# OC2_2boards.net
KiCad netlist of a schematic drawn in EAGLE
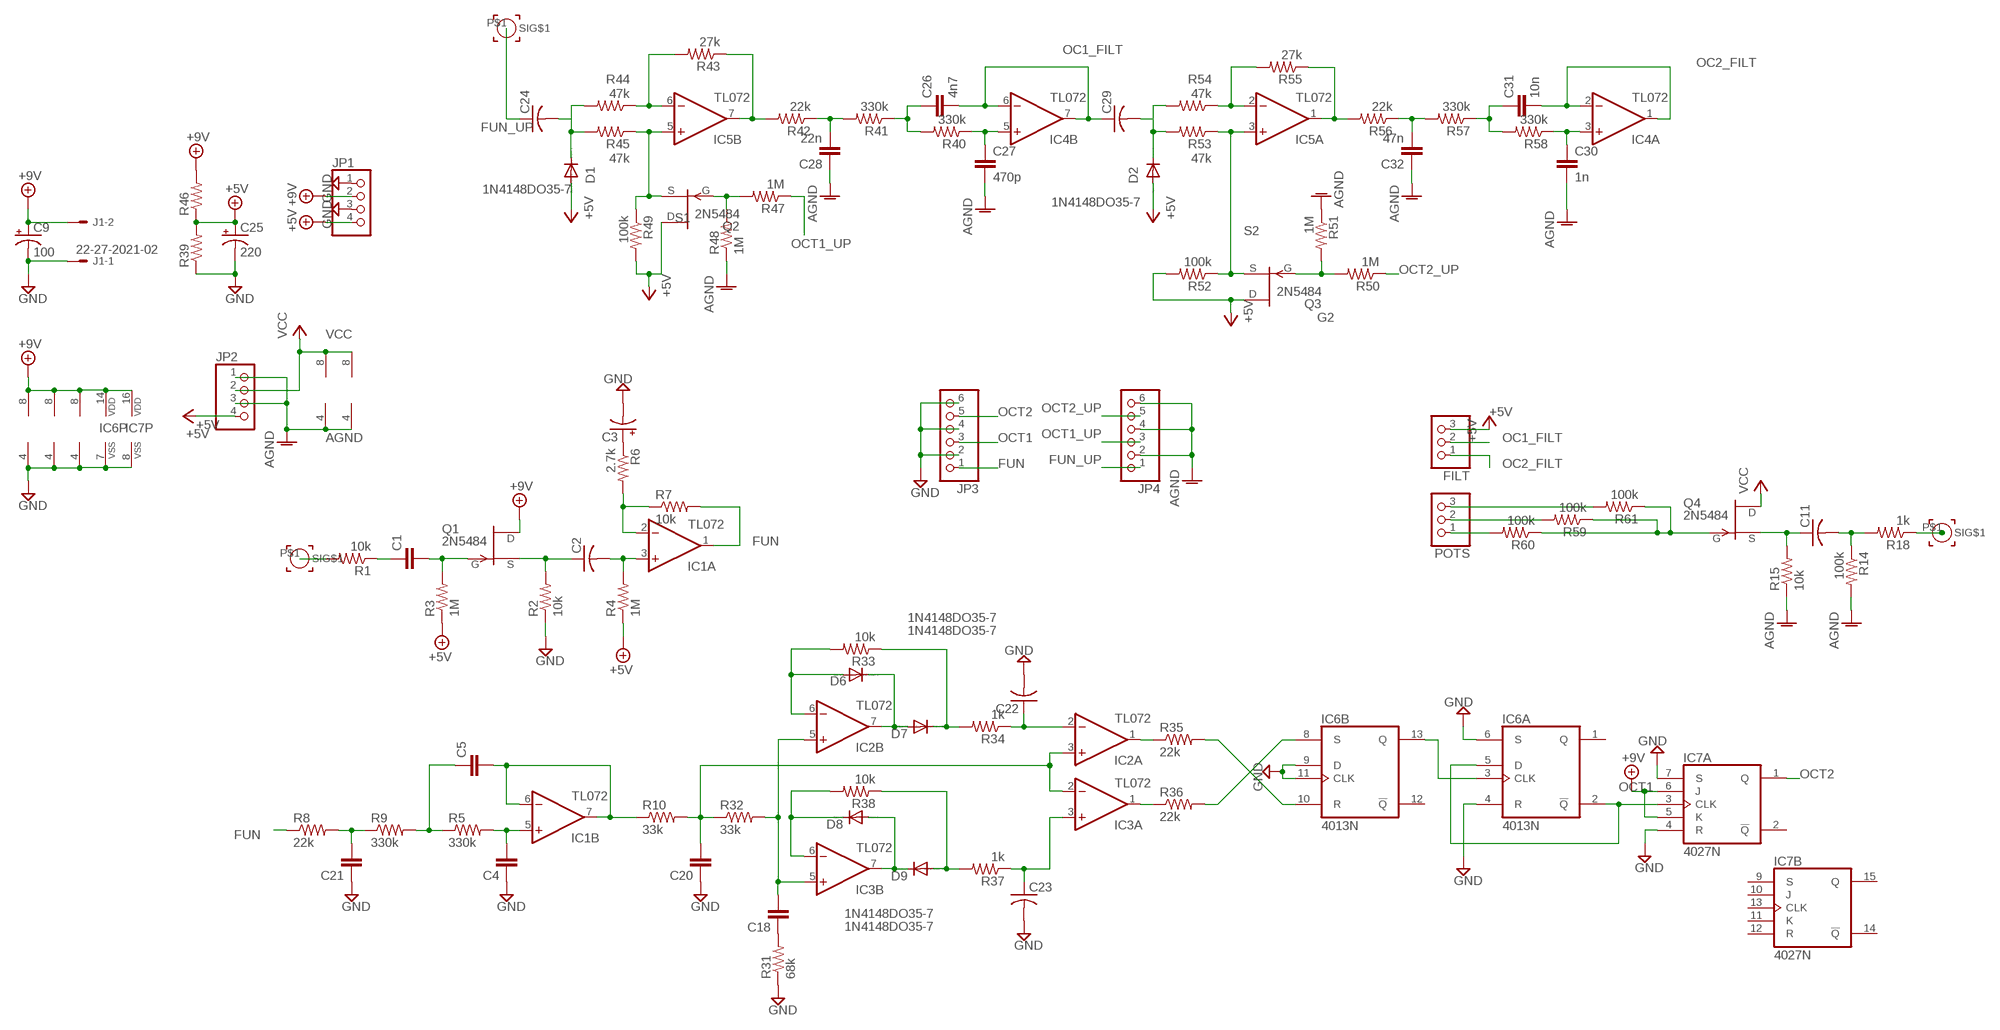
[diagram p0: schematic, sheet 1]

(export (version "E")
  (design (tool "Eeschema 10.0.6"))
  (components
    (comp (ref "C1")
      (value "C-EU")
      (footprint "eagle-import:C025-025X050-BP")
      (libsource (lib "eagle-import") (part "C-EU"))
    )
    (comp (ref "C2")
      (value "C-US")
      (footprint "eagle-import:C050-024X044-BP")
      (libsource (lib "eagle-import") (part "C-US"))
    )
    (comp (ref "C3")
      (value "CPOL-USE2.5-5")
      (footprint "eagle-import:E2,5-5")
      (libsource (lib "eagle-import") (part "CPOL-USE2.5-5"))
    )
    (comp (ref "C4")
      (value "C-EU")
      (footprint "eagle-import:C025-025X050-BP")
      (libsource (lib "eagle-import") (part "C-EU"))
    )
    (comp (ref "C5")
      (value "C-EU")
      (footprint "eagle-import:C025-025X050-BP")
      (libsource (lib "eagle-import") (part "C-EU"))
    )
    (comp (ref "C9")
      (value "100")
      (footprint "eagle-import:E2,5-6")
      (libsource (lib "eagle-import") (part "CPOL-USE2.5-6"))
    )
    (comp (ref "C11")
      (value "C-US")
      (footprint "eagle-import:C050-024X044-BP")
      (libsource (lib "eagle-import") (part "C-US"))
    )
    (comp (ref "C18")
      (value "C-EU")
      (footprint "eagle-import:C025-025X050-BP")
      (libsource (lib "eagle-import") (part "C-EU"))
    )
    (comp (ref "C20")
      (value "C-EU")
      (footprint "eagle-import:C025-025X050-BP")
      (libsource (lib "eagle-import") (part "C-EU"))
    )
    (comp (ref "C21")
      (value "C-EU")
      (footprint "eagle-import:C025-025X050-BP")
      (libsource (lib "eagle-import") (part "C-EU"))
    )
    (comp (ref "C22")
      (value "C-US")
      (footprint "eagle-import:C050-024X044-BP")
      (libsource (lib "eagle-import") (part "C-US"))
    )
    (comp (ref "C23")
      (value "C-US")
      (footprint "eagle-import:C050-024X044-BP")
      (libsource (lib "eagle-import") (part "C-US"))
    )
    (comp (ref "C24")
      (value "C-US")
      (footprint "eagle-import:C050-024X044-BP")
      (libsource (lib "eagle-import") (part "C-US"))
    )
    (comp (ref "C25")
      (value "220")
      (footprint "eagle-import:E3,5-8")
      (libsource (lib "eagle-import") (part "CPOL-USE3.5-8"))
    )
    (comp (ref "C26")
      (value "4n7")
      (footprint "eagle-import:C025-025X050-BP")
      (libsource (lib "eagle-import") (part "C-EU"))
    )
    (comp (ref "C27")
      (value "470p")
      (footprint "eagle-import:C025-025X050-BP")
      (libsource (lib "eagle-import") (part "C-EU"))
    )
    (comp (ref "C28")
      (value "22n")
      (footprint "eagle-import:C025-025X050-BP")
      (libsource (lib "eagle-import") (part "C-EU"))
    )
    (comp (ref "C29")
      (value "C-US")
      (footprint "eagle-import:C050-024X044-BP")
      (libsource (lib "eagle-import") (part "C-US"))
    )
    (comp (ref "C30")
      (value "1n")
      (footprint "eagle-import:C025-025X050-BP")
      (libsource (lib "eagle-import") (part "C-EU"))
    )
    (comp (ref "C31")
      (value "10n")
      (footprint "eagle-import:C025-025X050-BP")
      (libsource (lib "eagle-import") (part "C-EU"))
    )
    (comp (ref "C32")
      (value "47n")
      (footprint "eagle-import:C025-025X050-BP")
      (libsource (lib "eagle-import") (part "C-EU"))
    )
    (comp (ref "D1")
      (value "1N4148DO35-7")
      (footprint "eagle-import:DO35-7")
      (libsource (lib "eagle-import") (part "1N4148DO35-7"))
    )
    (comp (ref "D2")
      (value "1N4148DO35-7")
      (footprint "eagle-import:DO35-7")
      (libsource (lib "eagle-import") (part "1N4148DO35-7"))
    )
    (comp (ref "D6")
      (value "1N4148DO35-7")
      (footprint "eagle-import:DO35-7")
      (libsource (lib "eagle-import") (part "1N4148DO35-7"))
    )
    (comp (ref "D7")
      (value "1N4148DO35-7")
      (footprint "eagle-import:DO35-7")
      (libsource (lib "eagle-import") (part "1N4148DO35-7"))
    )
    (comp (ref "D8")
      (value "1N4148DO35-7")
      (footprint "eagle-import:DO35-7")
      (libsource (lib "eagle-import") (part "1N4148DO35-7"))
    )
    (comp (ref "D9")
      (value "1N4148DO35-7")
      (footprint "eagle-import:DO35-7")
      (libsource (lib "eagle-import") (part "1N4148DO35-7"))
    )
    (comp (ref "FILT")
      (value "PINHD-1X3")
      (footprint "eagle-import:1X03")
      (libsource (lib "eagle-import") (part "PINHD-1X3"))
    )
    (comp (ref "IC1")
      (value "TL072")
      (footprint "eagle-import:DIL08-BP")
      (libsource (lib "eagle-import") (part "TL072"))
    )
    (comp (ref "IC2")
      (value "TL072")
      (footprint "eagle-import:DIL08-BP")
      (libsource (lib "eagle-import") (part "TL072"))
    )
    (comp (ref "IC3")
      (value "TL072")
      (footprint "eagle-import:DIL08-BP")
      (libsource (lib "eagle-import") (part "TL072"))
    )
    (comp (ref "IC4")
      (value "TL072")
      (footprint "eagle-import:DIL08-BP")
      (libsource (lib "eagle-import") (part "TL072"))
    )
    (comp (ref "IC5")
      (value "TL072")
      (footprint "eagle-import:DIL08-BP")
      (libsource (lib "eagle-import") (part "TL072"))
    )
    (comp (ref "IC6")
      (value "4013N")
      (footprint "eagle-import:DIL14")
      (libsource (lib "eagle-import") (part "4013N"))
    )
    (comp (ref "IC7")
      (value "4027N")
      (footprint "eagle-import:DIL16")
      (libsource (lib "eagle-import") (part "4027N"))
    )
    (comp (ref "INPUT")
      (value "SIGNAL_PAD")
      (footprint "eagle-import:SIGNAL_PAD")
      (libsource (lib "eagle-import") (part "SIGNAL_PAD"))
    )
    (comp (ref "INPUT1")
      (value "SIGNAL_PAD")
      (footprint "eagle-import:SIGNAL_PAD")
      (libsource (lib "eagle-import") (part "SIGNAL_PAD"))
    )
    (comp (ref "INPUT2")
      (value "SIGNAL_PAD")
      (footprint "eagle-import:SIGNAL_PAD")
      (libsource (lib "eagle-import") (part "SIGNAL_PAD"))
    )
    (comp (ref "J1")
      (value "22-27-2021-02")
      (footprint "eagle-import:6410-02")
      (libsource (lib "eagle-import") (part "22-?-0227-2021"))
    )
    (comp (ref "JP1")
      (value "PINHD-1X4")
      (footprint "eagle-import:1X04")
      (libsource (lib "eagle-import") (part "PINHD-1X4"))
    )
    (comp (ref "JP2")
      (value "PINHD-1X4")
      (footprint "eagle-import:1X04")
      (libsource (lib "eagle-import") (part "PINHD-1X4"))
    )
    (comp (ref "JP3")
      (value "PINHD-1X6")
      (footprint "eagle-import:1X06")
      (libsource (lib "eagle-import") (part "PINHD-1X6"))
    )
    (comp (ref "JP4")
      (value "PINHD-1X6")
      (footprint "eagle-import:1X06")
      (libsource (lib "eagle-import") (part "PINHD-1X6"))
    )
    (comp (ref "POTS")
      (value "PINHD-1X3")
      (footprint "eagle-import:1X03")
      (libsource (lib "eagle-import") (part "PINHD-1X3"))
    )
    (comp (ref "Q1")
      (value "2N5484")
      (footprint "eagle-import:TO92-")
      (libsource (lib "eagle-import") (part "?5482N4"))
    )
    (comp (ref "Q2")
      (value "2N5484")
      (footprint "eagle-import:TO92-")
      (libsource (lib "eagle-import") (part "?5482N4"))
    )
    (comp (ref "Q3")
      (value "2N5484")
      (footprint "eagle-import:TO92-")
      (libsource (lib "eagle-import") (part "?5482N4"))
    )
    (comp (ref "Q4")
      (value "2N5484")
      (footprint "eagle-import:TO92-")
      (libsource (lib "eagle-import") (part "?5482N4"))
    )
    (comp (ref "R1")
      (value "10k")
      (footprint "eagle-import:0204V-BP")
      (libsource (lib "eagle-import") (part "R-US_0204/2V-BP"))
    )
    (comp (ref "R2")
      (value "10k")
      (footprint "eagle-import:0204V-BP")
      (libsource (lib "eagle-import") (part "R-US_0204/2V-BP"))
    )
    (comp (ref "R3")
      (value "1M")
      (footprint "eagle-import:0204V-BP")
      (libsource (lib "eagle-import") (part "R-US_0204/2V-BP"))
    )
    (comp (ref "R4")
      (value "1M")
      (footprint "eagle-import:0204_5-BP")
      (libsource (lib "eagle-import") (part "R-US_0204/5-BP"))
    )
    (comp (ref "R5")
      (value "330k")
      (footprint "eagle-import:0204V-BP")
      (libsource (lib "eagle-import") (part "R-US_0204/2V-BP"))
    )
    (comp (ref "R6")
      (value "2.7k")
      (footprint "eagle-import:0204V-BP")
      (libsource (lib "eagle-import") (part "R-US_0204/2V-BP"))
    )
    (comp (ref "R7")
      (value "10k")
      (footprint "eagle-import:0204V-BP")
      (libsource (lib "eagle-import") (part "R-US_0204/2V-BP"))
    )
    (comp (ref "R8")
      (value "22k")
      (footprint "eagle-import:0204V")
      (libsource (lib "eagle-import") (part "R-US_0204/2V"))
    )
    (comp (ref "R9")
      (value "330k")
      (footprint "eagle-import:0204_5-BP")
      (libsource (lib "eagle-import") (part "R-US_0204/5-BP"))
    )
    (comp (ref "R10")
      (value "33k")
      (footprint "eagle-import:0204V-BP")
      (libsource (lib "eagle-import") (part "R-US_0204/2V-BP"))
    )
    (comp (ref "R14")
      (value "100k")
      (footprint "eagle-import:0204_5-BP")
      (libsource (lib "eagle-import") (part "R-US_0204/5-BP"))
    )
    (comp (ref "R15")
      (value "10k")
      (footprint "eagle-import:0204V-BP")
      (libsource (lib "eagle-import") (part "R-US_0204/2V-BP"))
    )
    (comp (ref "R18")
      (value "1k")
      (footprint "eagle-import:0204V-BP")
      (libsource (lib "eagle-import") (part "R-US_0204/2V-BP"))
    )
    (comp (ref "R31")
      (value "68k")
      (footprint "eagle-import:0204V-BP")
      (libsource (lib "eagle-import") (part "R-US_0204/2V-BP"))
    )
    (comp (ref "R32")
      (value "33k")
      (footprint "eagle-import:0204V-BP")
      (libsource (lib "eagle-import") (part "R-US_0204/2V-BP"))
    )
    (comp (ref "R33")
      (value "10k")
      (footprint "eagle-import:0204V-BP")
      (libsource (lib "eagle-import") (part "R-US_0204/2V-BP"))
    )
    (comp (ref "R34")
      (value "1k")
      (footprint "eagle-import:0204V-BP")
      (libsource (lib "eagle-import") (part "R-US_0204/2V-BP"))
    )
    (comp (ref "R35")
      (value "22k")
      (footprint "eagle-import:0204_5-BP")
      (libsource (lib "eagle-import") (part "R-US_0204/5-BP"))
    )
    (comp (ref "R36")
      (value "22k")
      (footprint "eagle-import:0204_5-BP")
      (libsource (lib "eagle-import") (part "R-US_0204/5-BP"))
    )
    (comp (ref "R37")
      (value "1k")
      (footprint "eagle-import:0204V-BP")
      (libsource (lib "eagle-import") (part "R-US_0204/2V-BP"))
    )
    (comp (ref "R38")
      (value "10k")
      (footprint "eagle-import:0204V-BP")
      (libsource (lib "eagle-import") (part "R-US_0204/2V-BP"))
    )
    (comp (ref "R39")
      (value "R-US_0204/2V-BP")
      (footprint "eagle-import:0204V-BP")
      (libsource (lib "eagle-import") (part "R-US_0204/2V-BP"))
    )
    (comp (ref "R40")
      (value "330k")
      (footprint "eagle-import:0204V-BP")
      (libsource (lib "eagle-import") (part "R-US_0204/2V-BP"))
    )
    (comp (ref "R41")
      (value "330k")
      (footprint "eagle-import:0204V-BP")
      (libsource (lib "eagle-import") (part "R-US_0204/2V-BP"))
    )
    (comp (ref "R42")
      (value "22k")
      (footprint "eagle-import:0204_5-BP")
      (libsource (lib "eagle-import") (part "R-US_0204/5-BP"))
    )
    (comp (ref "R43")
      (value "27k")
      (footprint "eagle-import:0204V-BP")
      (libsource (lib "eagle-import") (part "R-US_0204/2V-BP"))
    )
    (comp (ref "R44")
      (value "47k")
      (footprint "eagle-import:0204V-BP")
      (libsource (lib "eagle-import") (part "R-US_0204/2V-BP"))
    )
    (comp (ref "R45")
      (value "47k")
      (footprint "eagle-import:0204V-BP")
      (libsource (lib "eagle-import") (part "R-US_0204/2V-BP"))
    )
    (comp (ref "R46")
      (value "R-US_0204/2V-BP")
      (footprint "eagle-import:0204V-BP")
      (libsource (lib "eagle-import") (part "R-US_0204/2V-BP"))
    )
    (comp (ref "R47")
      (value "1M")
      (footprint "eagle-import:0204_5-BP")
      (libsource (lib "eagle-import") (part "R-US_0204/5-BP"))
    )
    (comp (ref "R48")
      (value "1M")
      (footprint "eagle-import:0204_5-BP")
      (libsource (lib "eagle-import") (part "R-US_0204/5-BP"))
    )
    (comp (ref "R49")
      (value "100k")
      (footprint "eagle-import:0204V-BP")
      (libsource (lib "eagle-import") (part "R-US_0204/2V-BP"))
    )
    (comp (ref "R50")
      (value "1M")
      (footprint "eagle-import:0204_5-BP")
      (libsource (lib "eagle-import") (part "R-US_0204/5-BP"))
    )
    (comp (ref "R51")
      (value "1M")
      (footprint "eagle-import:0204_5-BP")
      (libsource (lib "eagle-import") (part "R-US_0204/5-BP"))
    )
    (comp (ref "R52")
      (value "100k")
      (footprint "eagle-import:0204V-BP")
      (libsource (lib "eagle-import") (part "R-US_0204/2V-BP"))
    )
    (comp (ref "R53")
      (value "47k")
      (footprint "eagle-import:0204V-BP")
      (libsource (lib "eagle-import") (part "R-US_0204/2V-BP"))
    )
    (comp (ref "R54")
      (value "47k")
      (footprint "eagle-import:0204V-BP")
      (libsource (lib "eagle-import") (part "R-US_0204/2V-BP"))
    )
    (comp (ref "R55")
      (value "27k")
      (footprint "eagle-import:0204V-BP")
      (libsource (lib "eagle-import") (part "R-US_0204/2V-BP"))
    )
    (comp (ref "R56")
      (value "22k")
      (footprint "eagle-import:0204_5-BP")
      (libsource (lib "eagle-import") (part "R-US_0204/5-BP"))
    )
    (comp (ref "R57")
      (value "330k")
      (footprint "eagle-import:0204V-BP")
      (libsource (lib "eagle-import") (part "R-US_0204/2V-BP"))
    )
    (comp (ref "R58")
      (value "330k")
      (footprint "eagle-import:0204V-BP")
      (libsource (lib "eagle-import") (part "R-US_0204/2V-BP"))
    )
    (comp (ref "R59")
      (value "100k")
      (footprint "eagle-import:0204V-BP")
      (libsource (lib "eagle-import") (part "R-US_0204/2V-BP"))
    )
    (comp (ref "R60")
      (value "100k")
      (footprint "eagle-import:0204V-BP")
      (libsource (lib "eagle-import") (part "R-US_0204/2V-BP"))
    )
    (comp (ref "R61")
      (value "100k")
      (footprint "eagle-import:0204V-BP")
      (libsource (lib "eagle-import") (part "R-US_0204/2V-BP"))
    )
  )
  (nets
    (net (code "1") (name "+5V") (class "Default")
      (node (ref "C25") (pin "+") (pinfunction "+_+") (pintype "passive"))
      (node (ref "D1") (pin "A") (pinfunction "A_A") (pintype "passive"))
      (node (ref "D2") (pin "A") (pinfunction "A_A") (pintype "passive"))
      (node (ref "FILT") (pin "3") (pinfunction "3_3") (pintype "passive"))
      (node (ref "JP1") (pin "4") (pinfunction "4_4") (pintype "passive"))
      (node (ref "JP2") (pin "4") (pinfunction "4_4") (pintype "passive"))
      (node (ref "Q2") (pin "3") (pinfunction "D_3") (pintype "passive"))
      (node (ref "Q3") (pin "3") (pinfunction "D_3") (pintype "passive"))
      (node (ref "R3") (pin "1") (pinfunction "1_1") (pintype "passive"))
      (node (ref "R39") (pin "2") (pinfunction "2_2") (pintype "passive"))
      (node (ref "R4") (pin "1") (pinfunction "1_1") (pintype "passive"))
      (node (ref "R46") (pin "1") (pinfunction "1_1") (pintype "passive"))
      (node (ref "R49") (pin "2") (pinfunction "2_2") (pintype "passive"))
      (node (ref "R52") (pin "2") (pinfunction "2_2") (pintype "passive"))
    )
    (net (code "2") (name "+9V") (class "Default")
      (node (ref "C9") (pin "+") (pinfunction "+_+") (pintype "passive"))
      (node (ref "IC1") (pin "8") (pinfunction "V+_8") (pintype "power_in"))
      (node (ref "IC2") (pin "8") (pinfunction "V+_8") (pintype "power_in"))
      (node (ref "IC3") (pin "8") (pinfunction "V+_8") (pintype "power_in"))
      (node (ref "IC6") (pin "14") (pinfunction "VDD_14") (pintype "power_in"))
      (node (ref "IC7") (pin "16") (pinfunction "VDD_16") (pintype "power_in"))
      (node (ref "IC7") (pin "5") (pinfunction "K_5") (pintype "input"))
      (node (ref "IC7") (pin "6") (pinfunction "J_6") (pintype "input"))
      (node (ref "J1") (pin "2") (pinfunction "S_2") (pintype "passive"))
      (node (ref "JP1") (pin "2") (pinfunction "2_2") (pintype "passive"))
      (node (ref "Q1") (pin "3") (pinfunction "D_3") (pintype "passive"))
      (node (ref "R46") (pin "2") (pinfunction "2_2") (pintype "passive"))
    )
    (net (code "3") (name "/FUN") (class "Default")
      (node (ref "IC1") (pin "1") (pinfunction "OUT_1") (pintype "output"))
      (node (ref "JP3") (pin "1") (pinfunction "1_1") (pintype "passive"))
      (node (ref "R7") (pin "2") (pinfunction "2_2") (pintype "passive"))
      (node (ref "R8") (pin "1") (pinfunction "1_1") (pintype "passive"))
    )
    (net (code "4") (name "/FUN_UP") (class "Default")
      (node (ref "C24") (pin "1") (pinfunction "1_1") (pintype "passive"))
      (node (ref "INPUT2") (pin "P$1") (pinfunction "SIG$1_P$1") (pintype "bidirectional"))
      (node (ref "JP4") (pin "1") (pinfunction "1_1") (pintype "passive"))
    )
    (net (code "5") (name "/G2") (class "Default")
      (node (ref "Q3") (pin "1") (pinfunction "G_1") (pintype "passive"))
      (node (ref "R50") (pin "2") (pinfunction "2_2") (pintype "passive"))
      (node (ref "R51") (pin "2") (pinfunction "2_2") (pintype "passive"))
    )
    (net (code "6") (name "/OC1_FILT") (class "Default")
      (node (ref "C26") (pin "2") (pinfunction "2_2") (pintype "passive"))
      (node (ref "C29") (pin "1") (pinfunction "1_1") (pintype "passive"))
      (node (ref "FILT") (pin "2") (pinfunction "2_2") (pintype "passive"))
      (node (ref "IC4") (pin "6") (pinfunction "-IN_6") (pintype "input"))
      (node (ref "IC4") (pin "7") (pinfunction "OUT_7") (pintype "output"))
    )
    (net (code "7") (name "/OC2_FILT") (class "Default")
      (node (ref "C31") (pin "2") (pinfunction "2_2") (pintype "passive"))
      (node (ref "FILT") (pin "1") (pinfunction "1_1") (pintype "passive"))
      (node (ref "IC4") (pin "1") (pinfunction "OUT_1") (pintype "output"))
      (node (ref "IC4") (pin "2") (pinfunction "-IN_2") (pintype "input"))
    )
    (net (code "8") (name "/OCT1") (class "Default")
      (node (ref "IC6") (pin "2") (pinfunction "~{Q}_2") (pintype "output"))
      (node (ref "IC6") (pin "5") (pinfunction "D_5") (pintype "input"))
      (node (ref "IC7") (pin "3") (pinfunction "CLK_3") (pintype "input"))
      (node (ref "JP3") (pin "3") (pinfunction "3_3") (pintype "passive"))
    )
    (net (code "9") (name "/OCT1_UP") (class "Default")
      (node (ref "JP4") (pin "3") (pinfunction "3_3") (pintype "passive"))
      (node (ref "R47") (pin "1") (pinfunction "1_1") (pintype "passive"))
    )
    (net (code "10") (name "/OCT2") (class "Default")
      (node (ref "IC7") (pin "1") (pinfunction "Q_1") (pintype "output"))
      (node (ref "JP3") (pin "5") (pinfunction "5_5") (pintype "passive"))
    )
    (net (code "11") (name "/OCT2_UP") (class "Default")
      (node (ref "JP4") (pin "5") (pinfunction "5_5") (pintype "passive"))
      (node (ref "R50") (pin "1") (pinfunction "1_1") (pintype "passive"))
    )
    (net (code "12") (name "/S1") (class "Default")
      (node (ref "IC5") (pin "5") (pinfunction "+IN_5") (pintype "input"))
      (node (ref "Q2") (pin "2") (pinfunction "S_2") (pintype "passive"))
      (node (ref "R45") (pin "1") (pinfunction "1_1") (pintype "passive"))
      (node (ref "R49") (pin "1") (pinfunction "1_1") (pintype "passive"))
    )
    (net (code "13") (name "/S2") (class "Default")
      (node (ref "IC5") (pin "3") (pinfunction "+IN_3") (pintype "input"))
      (node (ref "Q3") (pin "2") (pinfunction "S_2") (pintype "passive"))
      (node (ref "R52") (pin "1") (pinfunction "1_1") (pintype "passive"))
      (node (ref "R53") (pin "1") (pinfunction "1_1") (pintype "passive"))
    )
    (net (code "14") (name "AGND") (class "Default")
      (node (ref "C27") (pin "2") (pinfunction "2_2") (pintype "passive"))
      (node (ref "C28") (pin "1") (pinfunction "1_1") (pintype "passive"))
      (node (ref "C30") (pin "2") (pinfunction "2_2") (pintype "passive"))
      (node (ref "C32") (pin "1") (pinfunction "1_1") (pintype "passive"))
      (node (ref "IC4") (pin "4") (pinfunction "V-_4") (pintype "power_in"))
      (node (ref "IC5") (pin "4") (pinfunction "V-_4") (pintype "power_in"))
      (node (ref "JP2") (pin "1") (pinfunction "1_1") (pintype "passive"))
      (node (ref "JP2") (pin "3") (pinfunction "3_3") (pintype "passive"))
      (node (ref "JP4") (pin "2") (pinfunction "2_2") (pintype "passive"))
      (node (ref "JP4") (pin "4") (pinfunction "4_4") (pintype "passive"))
      (node (ref "JP4") (pin "6") (pinfunction "6_6") (pintype "passive"))
      (node (ref "R14") (pin "2") (pinfunction "2_2") (pintype "passive"))
      (node (ref "R15") (pin "1") (pinfunction "1_1") (pintype "passive"))
      (node (ref "R48") (pin "1") (pinfunction "1_1") (pintype "passive"))
      (node (ref "R51") (pin "1") (pinfunction "1_1") (pintype "passive"))
    )
    (net (code "15") (name "GND") (class "Default")
      (node (ref "C20") (pin "1") (pinfunction "1_1") (pintype "passive"))
      (node (ref "C21") (pin "1") (pinfunction "1_1") (pintype "passive"))
      (node (ref "C22") (pin "2") (pinfunction "2_2") (pintype "passive"))
      (node (ref "C23") (pin "2") (pinfunction "2_2") (pintype "passive"))
      (node (ref "C25") (pin "-") (pinfunction "-_-") (pintype "passive"))
      (node (ref "C3") (pin "-") (pinfunction "-_-") (pintype "passive"))
      (node (ref "C4") (pin "1") (pinfunction "1_1") (pintype "passive"))
      (node (ref "C9") (pin "-") (pinfunction "-_-") (pintype "passive"))
      (node (ref "IC1") (pin "4") (pinfunction "V-_4") (pintype "power_in"))
      (node (ref "IC2") (pin "4") (pinfunction "V-_4") (pintype "power_in"))
      (node (ref "IC3") (pin "4") (pinfunction "V-_4") (pintype "power_in"))
      (node (ref "IC6") (pin "11") (pinfunction "CLK_11") (pintype "input"))
      (node (ref "IC6") (pin "4") (pinfunction "R_4") (pintype "input"))
      (node (ref "IC6") (pin "6") (pinfunction "S_6") (pintype "input"))
      (node (ref "IC6") (pin "7") (pinfunction "VSS_7") (pintype "power_in"))
      (node (ref "IC6") (pin "9") (pinfunction "D_9") (pintype "input"))
      (node (ref "IC7") (pin "4") (pinfunction "R_4") (pintype "input"))
      (node (ref "IC7") (pin "7") (pinfunction "S_7") (pintype "input"))
      (node (ref "IC7") (pin "8") (pinfunction "VSS_8") (pintype "power_in"))
      (node (ref "J1") (pin "1") (pinfunction "S_1") (pintype "passive"))
      (node (ref "JP1") (pin "1") (pinfunction "1_1") (pintype "passive"))
      (node (ref "JP1") (pin "3") (pinfunction "3_3") (pintype "passive"))
      (node (ref "JP3") (pin "2") (pinfunction "2_2") (pintype "passive"))
      (node (ref "JP3") (pin "4") (pinfunction "4_4") (pintype "passive"))
      (node (ref "JP3") (pin "6") (pinfunction "6_6") (pintype "passive"))
      (node (ref "R2") (pin "1") (pinfunction "1_1") (pintype "passive"))
      (node (ref "R31") (pin "1") (pinfunction "1_1") (pintype "passive"))
      (node (ref "R39") (pin "1") (pinfunction "1_1") (pintype "passive"))
    )
    (net (code "16") (name "Net-(C1-Pad1)") (class "Default")
      (node (ref "C1") (pin "1") (pinfunction "1_1") (pintype "passive"))
      (node (ref "R1") (pin "1") (pinfunction "1_1") (pintype "passive"))
    )
    (net (code "17") (name "Net-(C3-Pad+)") (class "Default")
      (node (ref "C3") (pin "+") (pinfunction "+_+") (pintype "passive"))
      (node (ref "R6") (pin "1") (pinfunction "1_1") (pintype "passive"))
    )
    (net (code "18") (name "Net-(C5-Pad1)") (class "Default")
      (node (ref "C5") (pin "1") (pinfunction "1_1") (pintype "passive"))
      (node (ref "R5") (pin "1") (pinfunction "1_1") (pintype "passive"))
      (node (ref "R9") (pin "2") (pinfunction "2_2") (pintype "passive"))
    )
    (net (code "19") (name "Net-(C11-Pad2)") (class "Default")
      (node (ref "C11") (pin "2") (pinfunction "2_2") (pintype "passive"))
      (node (ref "R14") (pin "1") (pinfunction "1_1") (pintype "passive"))
      (node (ref "R18") (pin "2") (pinfunction "2_2") (pintype "passive"))
    )
    (net (code "20") (name "Net-(C18-Pad1)") (class "Default")
      (node (ref "C18") (pin "1") (pinfunction "1_1") (pintype "passive"))
      (node (ref "R31") (pin "2") (pinfunction "2_2") (pintype "passive"))
    )
    (net (code "21") (name "Net-(C21-Pad2)") (class "Default")
      (node (ref "C21") (pin "2") (pinfunction "2_2") (pintype "passive"))
      (node (ref "R8") (pin "2") (pinfunction "2_2") (pintype "passive"))
      (node (ref "R9") (pin "1") (pinfunction "1_1") (pintype "passive"))
    )
    (net (code "22") (name "Net-(C24-Pad2)") (class "Default")
      (node (ref "C24") (pin "2") (pinfunction "2_2") (pintype "passive"))
      (node (ref "D1") (pin "C") (pinfunction "C_C") (pintype "passive"))
      (node (ref "R44") (pin "2") (pinfunction "2_2") (pintype "passive"))
      (node (ref "R45") (pin "2") (pinfunction "2_2") (pintype "passive"))
    )
    (net (code "23") (name "Net-(C26-Pad1)") (class "Default")
      (node (ref "C26") (pin "1") (pinfunction "1_1") (pintype "passive"))
      (node (ref "R40") (pin "2") (pinfunction "2_2") (pintype "passive"))
      (node (ref "R41") (pin "1") (pinfunction "1_1") (pintype "passive"))
    )
    (net (code "24") (name "Net-(C28-Pad2)") (class "Default")
      (node (ref "C28") (pin "2") (pinfunction "2_2") (pintype "passive"))
      (node (ref "R41") (pin "2") (pinfunction "2_2") (pintype "passive"))
      (node (ref "R42") (pin "1") (pinfunction "1_1") (pintype "passive"))
    )
    (net (code "25") (name "Net-(C29-Pad2)") (class "Default")
      (node (ref "C29") (pin "2") (pinfunction "2_2") (pintype "passive"))
      (node (ref "D2") (pin "C") (pinfunction "C_C") (pintype "passive"))
      (node (ref "R53") (pin "2") (pinfunction "2_2") (pintype "passive"))
      (node (ref "R54") (pin "2") (pinfunction "2_2") (pintype "passive"))
    )
    (net (code "26") (name "Net-(C31-Pad1)") (class "Default")
      (node (ref "C31") (pin "1") (pinfunction "1_1") (pintype "passive"))
      (node (ref "R57") (pin "1") (pinfunction "1_1") (pintype "passive"))
      (node (ref "R58") (pin "2") (pinfunction "2_2") (pintype "passive"))
    )
    (net (code "27") (name "Net-(C32-Pad2)") (class "Default")
      (node (ref "C32") (pin "2") (pinfunction "2_2") (pintype "passive"))
      (node (ref "R56") (pin "1") (pinfunction "1_1") (pintype "passive"))
      (node (ref "R57") (pin "2") (pinfunction "2_2") (pintype "passive"))
    )
    (net (code "28") (name "Net-(D7-PadC)") (class "Default")
      (node (ref "D7") (pin "C") (pinfunction "C_C") (pintype "passive"))
      (node (ref "R33") (pin "1") (pinfunction "1_1") (pintype "passive"))
      (node (ref "R34") (pin "2") (pinfunction "2_2") (pintype "passive"))
    )
    (net (code "29") (name "Net-(D9-PadA)") (class "Default")
      (node (ref "D9") (pin "A") (pinfunction "A_A") (pintype "passive"))
      (node (ref "R37") (pin "2") (pinfunction "2_2") (pintype "passive"))
      (node (ref "R38") (pin "1") (pinfunction "1_1") (pintype "passive"))
    )
    (net (code "30") (name "Net-(IC1A-+IN)") (class "Default")
      (node (ref "C2") (pin "2") (pinfunction "2_2") (pintype "passive"))
      (node (ref "IC1") (pin "3") (pinfunction "+IN_3") (pintype "input"))
      (node (ref "R4") (pin "2") (pinfunction "2_2") (pintype "passive"))
    )
    (net (code "31") (name "Net-(IC1A--IN)") (class "Default")
      (node (ref "IC1") (pin "2") (pinfunction "-IN_2") (pintype "input"))
      (node (ref "R6") (pin "2") (pinfunction "2_2") (pintype "passive"))
      (node (ref "R7") (pin "1") (pinfunction "1_1") (pintype "passive"))
    )
    (net (code "32") (name "Net-(IC1B-+IN)") (class "Default")
      (node (ref "C4") (pin "2") (pinfunction "2_2") (pintype "passive"))
      (node (ref "IC1") (pin "5") (pinfunction "+IN_5") (pintype "input"))
      (node (ref "R5") (pin "2") (pinfunction "2_2") (pintype "passive"))
    )
    (net (code "33") (name "Net-(IC1B--IN)") (class "Default")
      (node (ref "C5") (pin "2") (pinfunction "2_2") (pintype "passive"))
      (node (ref "IC1") (pin "6") (pinfunction "-IN_6") (pintype "input"))
      (node (ref "IC1") (pin "7") (pinfunction "OUT_7") (pintype "output"))
      (node (ref "R10") (pin "1") (pinfunction "1_1") (pintype "passive"))
    )
    (net (code "34") (name "Net-(IC2A-+IN)") (class "Default")
      (node (ref "C20") (pin "2") (pinfunction "2_2") (pintype "passive"))
      (node (ref "IC2") (pin "3") (pinfunction "+IN_3") (pintype "input"))
      (node (ref "IC3") (pin "2") (pinfunction "-IN_2") (pintype "input"))
      (node (ref "R10") (pin "2") (pinfunction "2_2") (pintype "passive"))
      (node (ref "R32") (pin "1") (pinfunction "1_1") (pintype "passive"))
    )
    (net (code "35") (name "Net-(IC2A--IN)") (class "Default")
      (node (ref "C22") (pin "1") (pinfunction "1_1") (pintype "passive"))
      (node (ref "IC2") (pin "2") (pinfunction "-IN_2") (pintype "input"))
      (node (ref "R34") (pin "1") (pinfunction "1_1") (pintype "passive"))
    )
    (net (code "36") (name "Net-(IC2A-OUT)") (class "Default")
      (node (ref "IC2") (pin "1") (pinfunction "OUT_1") (pintype "output"))
      (node (ref "R35") (pin "1") (pinfunction "1_1") (pintype "passive"))
    )
    (net (code "37") (name "Net-(IC2B-+IN)") (class "Default")
      (node (ref "C18") (pin "2") (pinfunction "2_2") (pintype "passive"))
      (node (ref "IC2") (pin "5") (pinfunction "+IN_5") (pintype "input"))
      (node (ref "IC3") (pin "5") (pinfunction "+IN_5") (pintype "input"))
      (node (ref "R32") (pin "2") (pinfunction "2_2") (pintype "passive"))
    )
    (net (code "38") (name "Net-(IC2B--IN)") (class "Default")
      (node (ref "D6") (pin "A") (pinfunction "A_A") (pintype "passive"))
      (node (ref "IC2") (pin "6") (pinfunction "-IN_6") (pintype "input"))
      (node (ref "R33") (pin "2") (pinfunction "2_2") (pintype "passive"))
    )
    (net (code "39") (name "Net-(IC2B-OUT)") (class "Default")
      (node (ref "D6") (pin "C") (pinfunction "C_C") (pintype "passive"))
      (node (ref "D7") (pin "A") (pinfunction "A_A") (pintype "passive"))
      (node (ref "IC2") (pin "7") (pinfunction "OUT_7") (pintype "output"))
    )
    (net (code "40") (name "Net-(IC3A-+IN)") (class "Default")
      (node (ref "C23") (pin "1") (pinfunction "1_1") (pintype "passive"))
      (node (ref "IC3") (pin "3") (pinfunction "+IN_3") (pintype "input"))
      (node (ref "R37") (pin "1") (pinfunction "1_1") (pintype "passive"))
    )
    (net (code "41") (name "Net-(IC3A-OUT)") (class "Default")
      (node (ref "IC3") (pin "1") (pinfunction "OUT_1") (pintype "output"))
      (node (ref "R36") (pin "1") (pinfunction "1_1") (pintype "passive"))
    )
    (net (code "42") (name "Net-(IC3B--IN)") (class "Default")
      (node (ref "D8") (pin "C") (pinfunction "C_C") (pintype "passive"))
      (node (ref "IC3") (pin "6") (pinfunction "-IN_6") (pintype "input"))
      (node (ref "R38") (pin "2") (pinfunction "2_2") (pintype "passive"))
    )
    (net (code "43") (name "Net-(IC3B-OUT)") (class "Default")
      (node (ref "D8") (pin "A") (pinfunction "A_A") (pintype "passive"))
      (node (ref "D9") (pin "C") (pinfunction "C_C") (pintype "passive"))
      (node (ref "IC3") (pin "7") (pinfunction "OUT_7") (pintype "output"))
    )
    (net (code "44") (name "Net-(IC4A-+IN)") (class "Default")
      (node (ref "C30") (pin "1") (pinfunction "1_1") (pintype "passive"))
      (node (ref "IC4") (pin "3") (pinfunction "+IN_3") (pintype "input"))
      (node (ref "R58") (pin "1") (pinfunction "1_1") (pintype "passive"))
    )
    (net (code "45") (name "Net-(IC4B-+IN)") (class "Default")
      (node (ref "C27") (pin "1") (pinfunction "1_1") (pintype "passive"))
      (node (ref "IC4") (pin "5") (pinfunction "+IN_5") (pintype "input"))
      (node (ref "R40") (pin "1") (pinfunction "1_1") (pintype "passive"))
    )
    (net (code "46") (name "Net-(IC5A--IN)") (class "Default")
      (node (ref "IC5") (pin "2") (pinfunction "-IN_2") (pintype "input"))
      (node (ref "R54") (pin "1") (pinfunction "1_1") (pintype "passive"))
      (node (ref "R55") (pin "2") (pinfunction "2_2") (pintype "passive"))
    )
    (net (code "47") (name "Net-(IC5A-OUT)") (class "Default")
      (node (ref "IC5") (pin "1") (pinfunction "OUT_1") (pintype "output"))
      (node (ref "R55") (pin "1") (pinfunction "1_1") (pintype "passive"))
      (node (ref "R56") (pin "2") (pinfunction "2_2") (pintype "passive"))
    )
    (net (code "48") (name "Net-(IC5B--IN)") (class "Default")
      (node (ref "IC5") (pin "6") (pinfunction "-IN_6") (pintype "input"))
      (node (ref "R43") (pin "2") (pinfunction "2_2") (pintype "passive"))
      (node (ref "R44") (pin "1") (pinfunction "1_1") (pintype "passive"))
    )
    (net (code "49") (name "Net-(IC5B-OUT)") (class "Default")
      (node (ref "IC5") (pin "7") (pinfunction "OUT_7") (pintype "output"))
      (node (ref "R42") (pin "2") (pinfunction "2_2") (pintype "passive"))
      (node (ref "R43") (pin "1") (pinfunction "1_1") (pintype "passive"))
    )
    (net (code "50") (name "Net-(IC6A-CLK)") (class "Default")
      (node (ref "IC6") (pin "13") (pinfunction "Q_13") (pintype "output"))
      (node (ref "IC6") (pin "3") (pinfunction "CLK_3") (pintype "input"))
    )
    (net (code "51") (name "Net-(IC6B-R)") (class "Default")
      (node (ref "IC6") (pin "10") (pinfunction "R_10") (pintype "input"))
      (node (ref "R35") (pin "2") (pinfunction "2_2") (pintype "passive"))
    )
    (net (code "52") (name "Net-(IC6B-S)") (class "Default")
      (node (ref "IC6") (pin "8") (pinfunction "S_8") (pintype "input"))
      (node (ref "R36") (pin "2") (pinfunction "2_2") (pintype "passive"))
    )
    (net (code "53") (name "Net-(INPUT-SIG$1)") (class "Default")
      (node (ref "INPUT") (pin "P$1") (pinfunction "SIG$1_P$1") (pintype "bidirectional"))
      (node (ref "R1") (pin "2") (pinfunction "2_2") (pintype "passive"))
    )
    (net (code "54") (name "Net-(INPUT1-SIG$1)") (class "Default")
      (node (ref "INPUT1") (pin "P$1") (pinfunction "SIG$1_P$1") (pintype "bidirectional"))
      (node (ref "R18") (pin "1") (pinfunction "1_1") (pintype "passive"))
    )
    (net (code "55") (name "Net-(POTS-Pad1)") (class "Default")
      (node (ref "POTS") (pin "1") (pinfunction "1_1") (pintype "passive"))
      (node (ref "R60") (pin "2") (pinfunction "2_2") (pintype "passive"))
    )
    (net (code "56") (name "Net-(POTS-Pad2)") (class "Default")
      (node (ref "POTS") (pin "2") (pinfunction "2_2") (pintype "passive"))
      (node (ref "R59") (pin "2") (pinfunction "2_2") (pintype "passive"))
    )
    (net (code "57") (name "Net-(POTS-Pad3)") (class "Default")
      (node (ref "POTS") (pin "3") (pinfunction "3_3") (pintype "passive"))
      (node (ref "R61") (pin "2") (pinfunction "2_2") (pintype "passive"))
    )
    (net (code "58") (name "Net-(Q1-G)") (class "Default")
      (node (ref "C1") (pin "2") (pinfunction "2_2") (pintype "passive"))
      (node (ref "Q1") (pin "1") (pinfunction "G_1") (pintype "passive"))
      (node (ref "R3") (pin "2") (pinfunction "2_2") (pintype "passive"))
    )
    (net (code "59") (name "Net-(Q1-S)") (class "Default")
      (node (ref "C2") (pin "1") (pinfunction "1_1") (pintype "passive"))
      (node (ref "Q1") (pin "2") (pinfunction "S_2") (pintype "passive"))
      (node (ref "R2") (pin "2") (pinfunction "2_2") (pintype "passive"))
    )
    (net (code "60") (name "Net-(Q2-G)") (class "Default")
      (node (ref "Q2") (pin "1") (pinfunction "G_1") (pintype "passive"))
      (node (ref "R47") (pin "2") (pinfunction "2_2") (pintype "passive"))
      (node (ref "R48") (pin "2") (pinfunction "2_2") (pintype "passive"))
    )
    (net (code "61") (name "Net-(Q4-G)") (class "Default")
      (node (ref "Q4") (pin "1") (pinfunction "G_1") (pintype "passive"))
      (node (ref "R59") (pin "1") (pinfunction "1_1") (pintype "passive"))
      (node (ref "R60") (pin "1") (pinfunction "1_1") (pintype "passive"))
      (node (ref "R61") (pin "1") (pinfunction "1_1") (pintype "passive"))
    )
    (net (code "62") (name "Net-(Q4-S)") (class "Default")
      (node (ref "C11") (pin "1") (pinfunction "1_1") (pintype "passive"))
      (node (ref "Q4") (pin "2") (pinfunction "S_2") (pintype "passive"))
      (node (ref "R15") (pin "2") (pinfunction "2_2") (pintype "passive"))
    )
    (net (code "63") (name "VCC") (class "Default")
      (node (ref "IC4") (pin "8") (pinfunction "V+_8") (pintype "power_in"))
      (node (ref "IC5") (pin "8") (pinfunction "V+_8") (pintype "power_in"))
      (node (ref "JP2") (pin "2") (pinfunction "2_2") (pintype "passive"))
      (node (ref "Q4") (pin "3") (pinfunction "D_3") (pintype "passive"))
    )
    (net (code "64") (name "unconnected-(IC6A-Q-Pad1)") (class "Default")
      (node (ref "IC6") (pin "1") (pinfunction "Q_1") (pintype "output"))
    )
    (net (code "65") (name "unconnected-(IC6B-~{Q}-Pad12)") (class "Default")
      (node (ref "IC6") (pin "12") (pinfunction "~{Q}_12") (pintype "output"))
    )
    (net (code "66") (name "unconnected-(IC7A-~{Q}-Pad2)") (class "Default")
      (node (ref "IC7") (pin "2") (pinfunction "~{Q}_2") (pintype "output"))
    )
    (net (code "67") (name "unconnected-(IC7B-CLK-Pad13)") (class "Default")
      (node (ref "IC7") (pin "13") (pinfunction "CLK_13") (pintype "input"))
    )
    (net (code "68") (name "unconnected-(IC7B-J-Pad10)") (class "Default")
      (node (ref "IC7") (pin "10") (pinfunction "J_10") (pintype "input"))
    )
    (net (code "69") (name "unconnected-(IC7B-K-Pad11)") (class "Default")
      (node (ref "IC7") (pin "11") (pinfunction "K_11") (pintype "input"))
    )
    (net (code "70") (name "unconnected-(IC7B-Q-Pad15)") (class "Default")
      (node (ref "IC7") (pin "15") (pinfunction "Q_15") (pintype "output"))
    )
    (net (code "71") (name "unconnected-(IC7B-R-Pad12)") (class "Default")
      (node (ref "IC7") (pin "12") (pinfunction "R_12") (pintype "input"))
    )
    (net (code "72") (name "unconnected-(IC7B-S-Pad9)") (class "Default")
      (node (ref "IC7") (pin "9") (pinfunction "S_9") (pintype "input"))
    )
    (net (code "73") (name "unconnected-(IC7B-~{Q}-Pad14)") (class "Default")
      (node (ref "IC7") (pin "14") (pinfunction "~{Q}_14") (pintype "output"))
    )
  )
)
